# Battery_board_V4_4.net
KiCad netlist of a schematic drawn in EAGLE
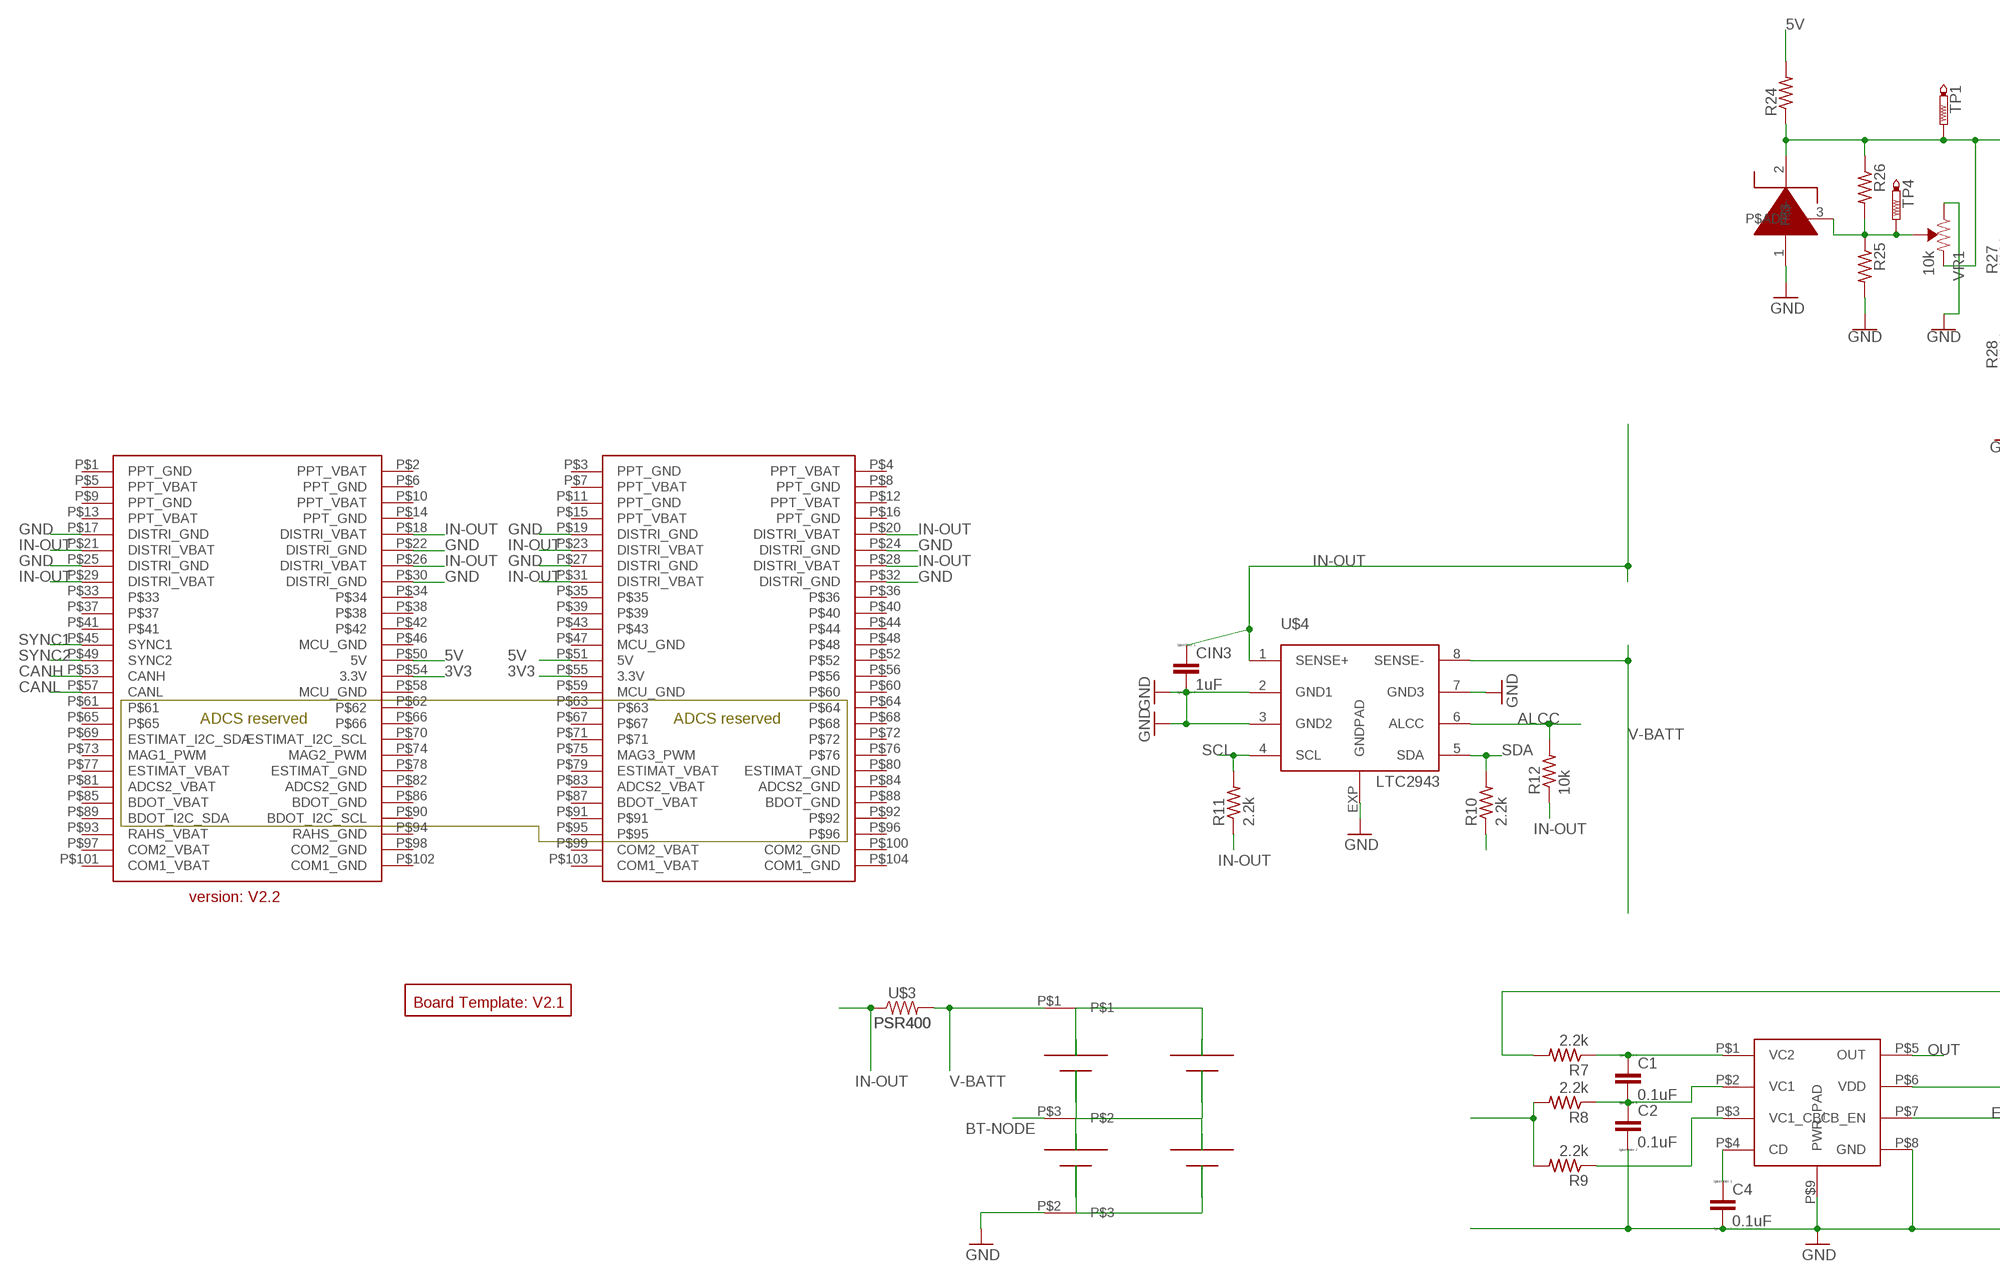
[diagram p0: schematic, sheet 1, part 1 of 2]
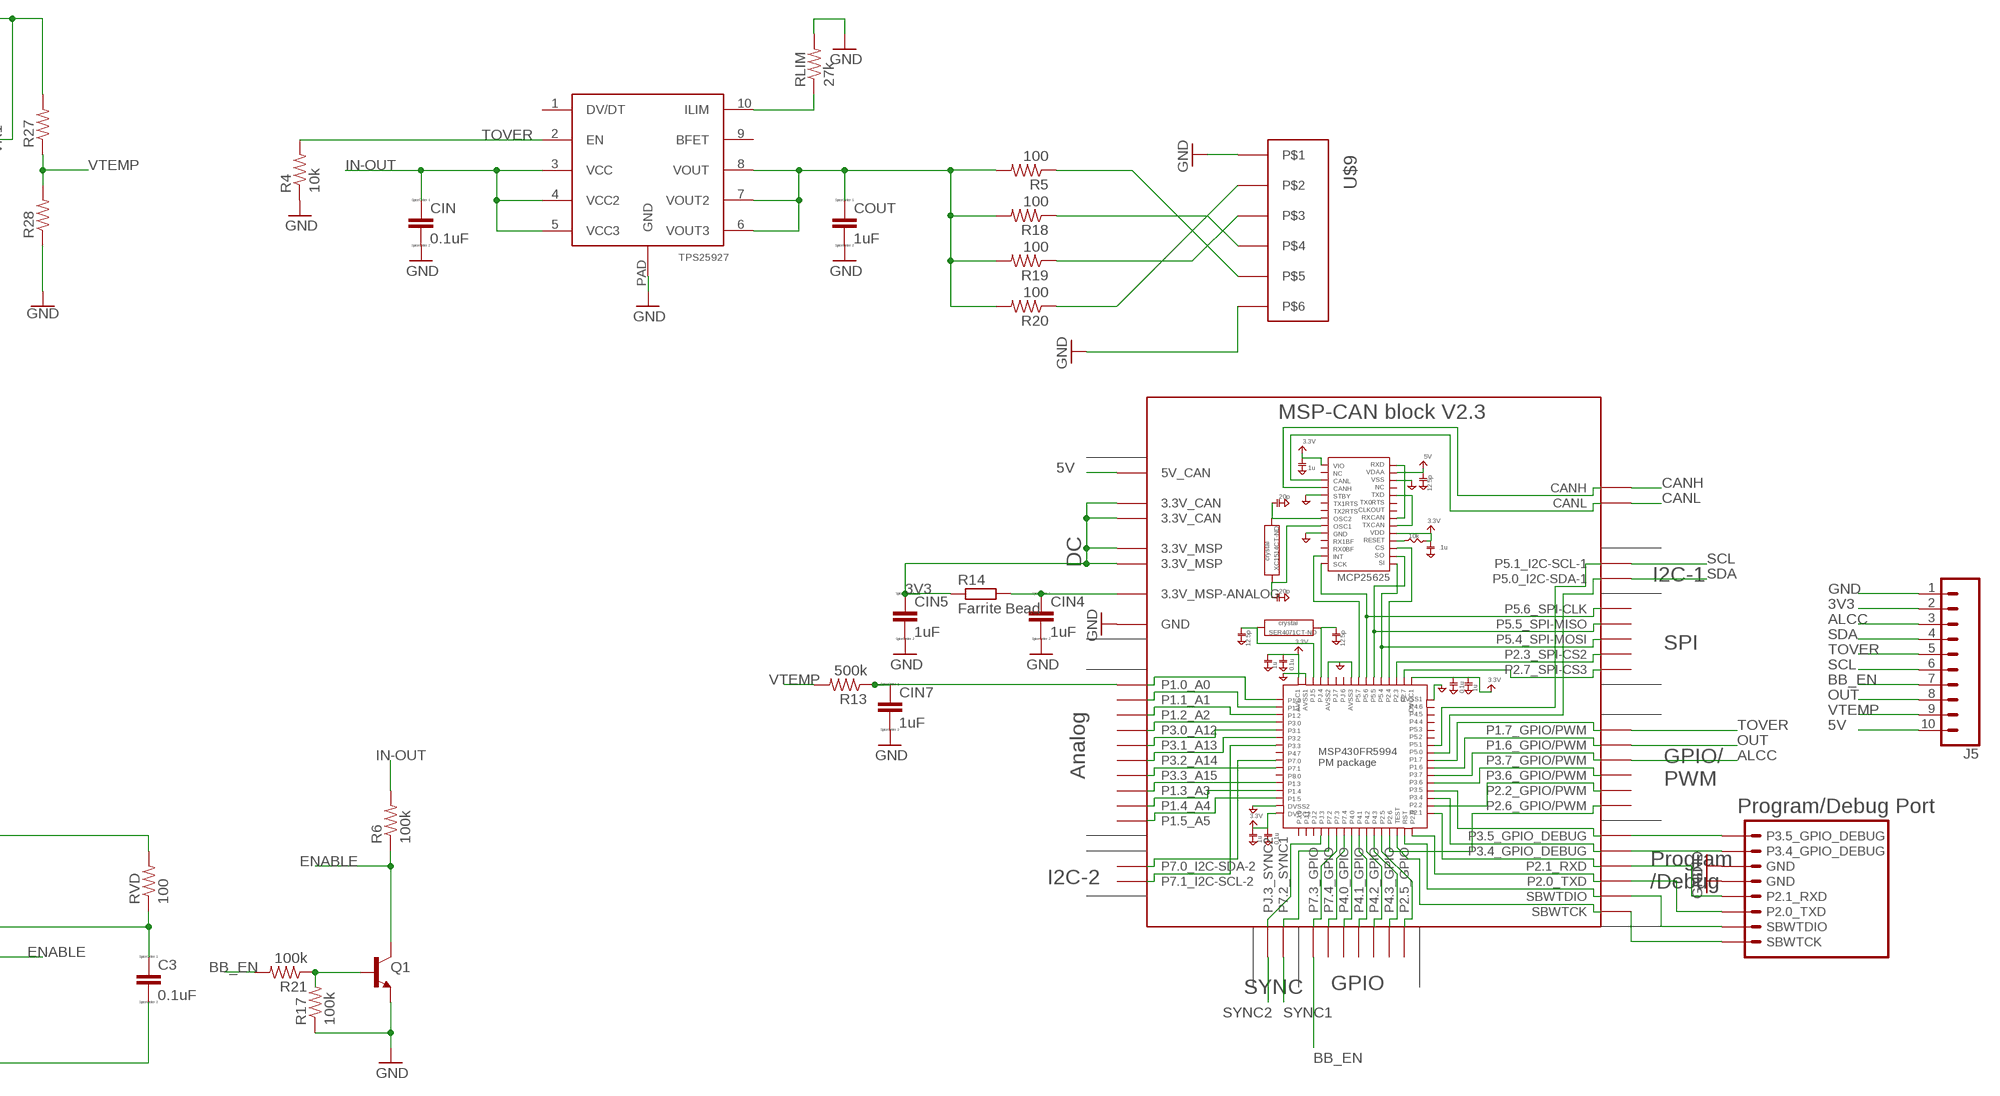
[diagram p1: schematic, sheet 1, part 2 of 2]

(export (version "E")
  (design (tool "Eeschema 10.0.6"))
  (components
    (comp (ref "C1")
      (value "0.1uF")
      (footprint "eagle-import:C0805")
      (libsource (lib "eagle-import") (part "C"))
    )
    (comp (ref "C2")
      (value "0.1uF")
      (footprint "eagle-import:C0805")
      (libsource (lib "eagle-import") (part "C"))
    )
    (comp (ref "C3")
      (value "0.1uF")
      (footprint "eagle-import:C0805")
      (libsource (lib "eagle-import") (part "C"))
    )
    (comp (ref "C4")
      (value "0.1uF")
      (footprint "eagle-import:C0805")
      (libsource (lib "eagle-import") (part "C"))
    )
    (comp (ref "CIN")
      (value "0.1uF")
      (footprint "eagle-import:C0805")
      (libsource (lib "eagle-import") (part "C"))
    )
    (comp (ref "CIN3")
      (value "1uF")
      (footprint "eagle-import:C0805")
      (libsource (lib "eagle-import") (part "C"))
    )
    (comp (ref "CIN4")
      (value "1uF")
      (footprint "eagle-import:C0805")
      (libsource (lib "eagle-import") (part "C"))
    )
    (comp (ref "CIN5")
      (value "1uF")
      (footprint "eagle-import:C0805")
      (libsource (lib "eagle-import") (part "C"))
    )
    (comp (ref "CIN7")
      (value "1uF")
      (footprint "eagle-import:C0805")
      (libsource (lib "eagle-import") (part "C"))
    )
    (comp (ref "COUT")
      (value "1uF")
      (footprint "eagle-import:C0805")
      (libsource (lib "eagle-import") (part "C"))
    )
    (comp (ref "J5")
      (value "CONN_10LOCK")
      (footprint "eagle-import:1X10_LOCK")
      (libsource (lib "eagle-import") (part "CONN_10LOCK"))
    )
    (comp (ref "Q1")
      (value "TRANS_NPN-MMBT2222AL")
      (footprint "eagle-import:SOT23-3")
      (libsource (lib "eagle-import") (part "TRANS_NPN-MMBT2222AL"))
    )
    (comp (ref "R4")
      (value "10k")
      (footprint "eagle-import:R0805")
      (libsource (lib "eagle-import") (part "R-US_R0805"))
    )
    (comp (ref "R5")
      (value "100")
      (footprint "eagle-import:R0805")
      (libsource (lib "eagle-import") (part "R-US_R0805"))
    )
    (comp (ref "R6")
      (value "100k")
      (footprint "eagle-import:R0805")
      (libsource (lib "eagle-import") (part "R-US_R0805"))
    )
    (comp (ref "R7")
      (value "2.2k")
      (footprint "eagle-import:R0805")
      (libsource (lib "eagle-import") (part "R-US_R0805"))
    )
    (comp (ref "R8")
      (value "2.2k")
      (footprint "eagle-import:R0805")
      (libsource (lib "eagle-import") (part "R-US_R0805"))
    )
    (comp (ref "R9")
      (value "2.2k")
      (footprint "eagle-import:R0805")
      (libsource (lib "eagle-import") (part "R-US_R0805"))
    )
    (comp (ref "R10")
      (value "2.2k")
      (footprint "eagle-import:R0805")
      (libsource (lib "eagle-import") (part "R-US_R0805"))
    )
    (comp (ref "R11")
      (value "2.2k")
      (footprint "eagle-import:R0805")
      (libsource (lib "eagle-import") (part "R-US_R0805"))
    )
    (comp (ref "R12")
      (value "10k")
      (footprint "eagle-import:R0805")
      (libsource (lib "eagle-import") (part "R-US_R0805"))
    )
    (comp (ref "R13")
      (value "500k")
      (footprint "eagle-import:R0805")
      (libsource (lib "eagle-import") (part "R-US_R0805"))
    )
    (comp (ref "R14")
      (value "Farrite Bead")
      (footprint "eagle-import:R1206")
      (libsource (lib "eagle-import") (part "R-EU_R1206"))
    )
    (comp (ref "R17")
      (value "100k")
      (footprint "eagle-import:M0805")
      (libsource (lib "eagle-import") (part "R-US_M0805"))
    )
    (comp (ref "R18")
      (value "100")
      (footprint "eagle-import:R0805")
      (libsource (lib "eagle-import") (part "R-US_R0805"))
    )
    (comp (ref "R19")
      (value "100")
      (footprint "eagle-import:R0805")
      (libsource (lib "eagle-import") (part "R-US_R0805"))
    )
    (comp (ref "R20")
      (value "100")
      (footprint "eagle-import:R0805")
      (libsource (lib "eagle-import") (part "R-US_R0805"))
    )
    (comp (ref "R21")
      (value "100k")
      (footprint "eagle-import:M0805")
      (libsource (lib "eagle-import") (part "R-US_M0805"))
    )
    (comp (ref "R24")
      (value "R-US_R0805")
      (footprint "eagle-import:R0805")
      (libsource (lib "eagle-import") (part "R-US_R0805"))
    )
    (comp (ref "R25")
      (value "R-US_R0805")
      (footprint "eagle-import:R0805")
      (libsource (lib "eagle-import") (part "R-US_R0805"))
    )
    (comp (ref "R26")
      (value "R-US_R0805")
      (footprint "eagle-import:R0805")
      (libsource (lib "eagle-import") (part "R-US_R0805"))
    )
    (comp (ref "R27")
      (value "R-US_R0805")
      (footprint "eagle-import:R0805")
      (libsource (lib "eagle-import") (part "R-US_R0805"))
    )
    (comp (ref "R28")
      (value "R-US_R0805")
      (footprint "eagle-import:R0805")
      (libsource (lib "eagle-import") (part "R-US_R0805"))
    )
    (comp (ref "RLIM")
      (value "27k")
      (footprint "eagle-import:R0805")
      (libsource (lib "eagle-import") (part "R-US_R0805"))
    )
    (comp (ref "RVD")
      (value "100")
      (footprint "eagle-import:R0805")
      (libsource (lib "eagle-import") (part "R-US_R0805"))
    )
    (comp (ref "TP1")
      (value "PTR1PAD1-13Y")
      (footprint "eagle-import:P1-13Y")
      (libsource (lib "eagle-import") (part "PTR1PAD1-13Y"))
    )
    (comp (ref "TP4")
      (value "PTR1PAD1-13Y")
      (footprint "eagle-import:P1-13Y")
      (libsource (lib "eagle-import") (part "PTR1PAD1-13Y"))
    )
    (comp (ref "U$1")
      (value "MSP-CAN_BLOCK")
      (footprint "eagle-import:MSP-CAN_BLOCK")
      (libsource (lib "eagle-import") (part "MSP-CAN_BLOCK"))
    )
    (comp (ref "U$2")
      (value "PROGRAM/DEBUG_PORT")
      (footprint "eagle-import:1X08_CONNECTOR")
      (libsource (lib "eagle-import") (part "PROGRAM/DEBUG_PORT"))
    )
    (comp (ref "U$3")
      (value "PSR400")
      (footprint "eagle-import:PSR400")
      (libsource (lib "eagle-import") (part "PSR400"))
    )
    (comp (ref "U$4")
      (value "LTC2943")
      (footprint "eagle-import:DFN8(3X3)LT")
      (libsource (lib "eagle-import") (part "LTC2943"))
    )
    (comp (ref "U$5")
      (value "TPS252927")
      (footprint "eagle-import:VSON10")
      (libsource (lib "eagle-import") (part "TPS252927"))
    )
    (comp (ref "U$6")
      (value "POWER_PACK")
      (footprint "eagle-import:BATTERY_PACK")
      (libsource (lib "eagle-import") (part "POWER_PACK"))
    )
    (comp (ref "U$7")
      (value "PC104_CONNECTOR")
      (footprint "eagle-import:PC104_CONNECTOR")
      (libsource (lib "eagle-import") (part "PC104_CONNECTOR"))
    )
    (comp (ref "U$8")
      (value "BQ29209")
      (footprint "eagle-import:VSON8")
      (libsource (lib "eagle-import") (part "BQ29209"))
    )
    (comp (ref "U$9")
      (value "PICOLOCK_6")
      (footprint "eagle-import:PICOLOCK_6")
      (libsource (lib "eagle-import") (part "PICOLOCK_6"))
    )
    (comp (ref "U$10")
      (value "LM135Z")
      (footprint "eagle-import:TO-92-3")
      (libsource (lib "eagle-import") (part "LM135Z"))
    )
    (comp (ref "U$11")
      (value "BOARD_TEMPLATE")
      (footprint "eagle-import:BOARD_TEMPLATE")
      (libsource (lib "eagle-import") (part "BOARD_TEMPLATE"))
    )
    (comp (ref "VR1")
      (value "10k")
      (footprint "eagle-import:TRIMPOT-SMD-TC33X")
      (libsource (lib "eagle-import") (part "TRIMPOT-SMD-3MM-OPEN-1/10W-25%"))
    )
  )
  (nets
    (net (code "1") (name "/3V3") (class "Default")
      (node (ref "CIN5") (pin "1") (pinfunction "1_1") (pintype "passive"))
      (node (ref "J5") (pin "2") (pinfunction "2_2") (pintype "passive"))
      (node (ref "R14") (pin "1") (pinfunction "1_1") (pintype "passive"))
      (node (ref "U$1") (pin "3.3V@CAN1") (pinfunction "3.3V_CAN_3.3V@CAN1") (pintype "bidirectional"))
      (node (ref "U$1") (pin "3.3V@CAN2") (pinfunction "3.3V_CAN_3.3V@CAN2") (pintype "bidirectional"))
      (node (ref "U$1") (pin "3.3V@MSP1") (pinfunction "3.3V_MSP_3.3V@MSP1") (pintype "bidirectional"))
      (node (ref "U$1") (pin "3.3V@MSP2") (pinfunction "3.3V_MSP_3.3V@MSP2") (pintype "bidirectional"))
      (node (ref "U$7") (pin "P$54") (pinfunction "3.3V_P$54") (pintype "bidirectional"))
      (node (ref "U$7") (pin "P$55") (pinfunction "3.3V_P$55") (pintype "bidirectional"))
    )
    (net (code "2") (name "/5V") (class "Default")
      (node (ref "J5") (pin "10") (pinfunction "10_10") (pintype "passive"))
      (node (ref "R24") (pin "2") (pinfunction "2_2") (pintype "passive"))
      (node (ref "U$1") (pin "5V") (pinfunction "5V_CAN_5V") (pintype "bidirectional"))
      (node (ref "U$7") (pin "P$50") (pinfunction "5V_P$50") (pintype "bidirectional"))
      (node (ref "U$7") (pin "P$51") (pinfunction "5V_P$51") (pintype "bidirectional"))
    )
    (net (code "3") (name "/ALCC") (class "Default")
      (node (ref "J5") (pin "3") (pinfunction "3_3") (pintype "passive"))
      (node (ref "R12") (pin "2") (pinfunction "2_2") (pintype "passive"))
      (node (ref "U$1") (pin "P3.7_GPIO/PWM") (pinfunction "P3.7_GPIO/PWM_P3.7_GPIO/PWM") (pintype "bidirectional"))
      (node (ref "U$4") (pin "6") (pinfunction "ALCC_6") (pintype "bidirectional"))
    )
    (net (code "4") (name "/BB_EN") (class "Default")
      (node (ref "J5") (pin "7") (pinfunction "7_7") (pintype "passive"))
      (node (ref "R21") (pin "2") (pinfunction "2_2") (pintype "passive"))
      (node (ref "U$1") (pin "P7.3_GPIO") (pinfunction "P7.3_GPIO_P7.3_GPIO") (pintype "bidirectional"))
    )
    (net (code "5") (name "/BT-NODE") (class "Default")
      (node (ref "R8") (pin "2") (pinfunction "2_2") (pintype "passive"))
      (node (ref "R9") (pin "2") (pinfunction "2_2") (pintype "passive"))
      (node (ref "U$6") (pin "P$3") (pinfunction "P$2_P$3") (pintype "bidirectional"))
    )
    (net (code "6") (name "/CANH") (class "Default")
      (node (ref "U$1") (pin "CANH") (pinfunction "CANH_CANH") (pintype "bidirectional"))
      (node (ref "U$7") (pin "P$53") (pinfunction "CANH_P$53") (pintype "bidirectional"))
    )
    (net (code "7") (name "/CANL") (class "Default")
      (node (ref "U$1") (pin "CANL") (pinfunction "CANL_CANL") (pintype "bidirectional"))
      (node (ref "U$7") (pin "P$57") (pinfunction "CANL_P$57") (pintype "bidirectional"))
    )
    (net (code "8") (name "/ENABLE") (class "Default")
      (node (ref "Q1") (pin "3") (pinfunction "C_3") (pintype "passive"))
      (node (ref "R6") (pin "1") (pinfunction "1_1") (pintype "passive"))
      (node (ref "U$8") (pin "P$7") (pinfunction "CB_EN_P$7") (pintype "bidirectional"))
    )
    (net (code "9") (name "/IN-OUT") (class "Default")
      (node (ref "CIN") (pin "1") (pinfunction "1_1") (pintype "passive"))
      (node (ref "CIN3") (pin "1") (pinfunction "1_1") (pintype "passive"))
      (node (ref "R10") (pin "1") (pinfunction "1_1") (pintype "passive"))
      (node (ref "R11") (pin "1") (pinfunction "1_1") (pintype "passive"))
      (node (ref "R12") (pin "1") (pinfunction "1_1") (pintype "passive"))
      (node (ref "R6") (pin "2") (pinfunction "2_2") (pintype "passive"))
      (node (ref "R7") (pin "2") (pinfunction "2_2") (pintype "passive"))
      (node (ref "RVD") (pin "2") (pinfunction "2_2") (pintype "passive"))
      (node (ref "U$3") (pin "P$1") (pinfunction "1_P$1") (pintype "passive"))
      (node (ref "U$4") (pin "1") (pinfunction "SENSE+_1") (pintype "bidirectional"))
      (node (ref "U$5") (pin "3") (pinfunction "VCC_3") (pintype "bidirectional"))
      (node (ref "U$5") (pin "4") (pinfunction "VCC2_4") (pintype "bidirectional"))
      (node (ref "U$5") (pin "5") (pinfunction "VCC3_5") (pintype "bidirectional"))
      (node (ref "U$7") (pin "P$18") (pinfunction "DISTRI_VBAT_P$18") (pintype "bidirectional"))
      (node (ref "U$7") (pin "P$20") (pinfunction "DISTRI_VBAT_P$20") (pintype "bidirectional"))
      (node (ref "U$7") (pin "P$21") (pinfunction "DISTRI_VBAT_P$21") (pintype "bidirectional"))
      (node (ref "U$7") (pin "P$23") (pinfunction "DISTRI_VBAT_P$23") (pintype "bidirectional"))
      (node (ref "U$7") (pin "P$26") (pinfunction "DISTRI_VBAT_P$26") (pintype "bidirectional"))
      (node (ref "U$7") (pin "P$28") (pinfunction "DISTRI_VBAT_P$28") (pintype "bidirectional"))
      (node (ref "U$7") (pin "P$29") (pinfunction "DISTRI_VBAT_P$29") (pintype "bidirectional"))
      (node (ref "U$7") (pin "P$31") (pinfunction "DISTRI_VBAT_P$31") (pintype "bidirectional"))
    )
    (net (code "10") (name "/OUT") (class "Default")
      (node (ref "J5") (pin "8") (pinfunction "8_8") (pintype "passive"))
      (node (ref "U$1") (pin "P1.6_GPIO/PWM") (pinfunction "P1.6_GPIO/PWM_P1.6_GPIO/PWM") (pintype "bidirectional"))
      (node (ref "U$8") (pin "P$5") (pinfunction "OUT_P$5") (pintype "bidirectional"))
    )
    (net (code "11") (name "/SCL") (class "Default")
      (node (ref "J5") (pin "6") (pinfunction "6_6") (pintype "passive"))
      (node (ref "R11") (pin "2") (pinfunction "2_2") (pintype "passive"))
      (node (ref "U$1") (pin "P5.1_I2C-SCL-1") (pinfunction "P5.1_I2C-SCL-1_P5.1_I2C-SCL-1") (pintype "bidirectional"))
      (node (ref "U$4") (pin "4") (pinfunction "SCL_4") (pintype "bidirectional"))
    )
    (net (code "12") (name "/SDA") (class "Default")
      (node (ref "J5") (pin "4") (pinfunction "4_4") (pintype "passive"))
      (node (ref "R10") (pin "2") (pinfunction "2_2") (pintype "passive"))
      (node (ref "U$1") (pin "P5.0_I2C-SDA-1") (pinfunction "P5.0_I2C-SDA-1_P5.0_I2C-SDA-1") (pintype "bidirectional"))
      (node (ref "U$4") (pin "5") (pinfunction "SDA_5") (pintype "bidirectional"))
    )
    (net (code "13") (name "/SYNC1") (class "Default")
      (node (ref "U$1") (pin "P7.2_SYNC1") (pinfunction "P7.2_SYNC1_P7.2_SYNC1") (pintype "bidirectional"))
      (node (ref "U$7") (pin "P$45") (pinfunction "SYNC1_P$45") (pintype "bidirectional"))
    )
    (net (code "14") (name "/SYNC2") (class "Default")
      (node (ref "U$1") (pin "PJ.3_SYNC2") (pinfunction "PJ.3_SYNC2_PJ.3_SYNC2") (pintype "bidirectional"))
      (node (ref "U$7") (pin "P$49") (pinfunction "SYNC2_P$49") (pintype "bidirectional"))
    )
    (net (code "15") (name "/TOVER") (class "Default")
      (node (ref "J5") (pin "5") (pinfunction "5_5") (pintype "passive"))
      (node (ref "R4") (pin "2") (pinfunction "2_2") (pintype "passive"))
      (node (ref "U$1") (pin "P1.7_GPIO/PWM") (pinfunction "P1.7_GPIO/PWM_P1.7_GPIO/PWM") (pintype "bidirectional"))
      (node (ref "U$5") (pin "2") (pinfunction "EN_2") (pintype "bidirectional"))
    )
    (net (code "16") (name "/V-BATT") (class "Default")
      (node (ref "U$3") (pin "P$2") (pinfunction "2_P$2") (pintype "passive"))
      (node (ref "U$4") (pin "8") (pinfunction "SENSE-_8") (pintype "bidirectional"))
      (node (ref "U$6") (pin "P$1") (pinfunction "P$1_P$1") (pintype "bidirectional"))
    )
    (net (code "17") (name "/VTEMP") (class "Default")
      (node (ref "J5") (pin "9") (pinfunction "9_9") (pintype "passive"))
      (node (ref "R13") (pin "2") (pinfunction "2_2") (pintype "passive"))
      (node (ref "R27") (pin "1") (pinfunction "1_1") (pintype "passive"))
      (node (ref "R28") (pin "2") (pinfunction "2_2") (pintype "passive"))
    )
    (net (code "18") (name "GND") (class "Default")
      (node (ref "C2") (pin "2") (pinfunction "2_2") (pintype "passive"))
      (node (ref "C3") (pin "2") (pinfunction "2_2") (pintype "passive"))
      (node (ref "C4") (pin "2") (pinfunction "2_2") (pintype "passive"))
      (node (ref "CIN") (pin "2") (pinfunction "2_2") (pintype "passive"))
      (node (ref "CIN3") (pin "2") (pinfunction "2_2") (pintype "passive"))
      (node (ref "CIN4") (pin "2") (pinfunction "2_2") (pintype "passive"))
      (node (ref "CIN5") (pin "2") (pinfunction "2_2") (pintype "passive"))
      (node (ref "CIN7") (pin "2") (pinfunction "2_2") (pintype "passive"))
      (node (ref "COUT") (pin "2") (pinfunction "2_2") (pintype "passive"))
      (node (ref "J5") (pin "1") (pinfunction "1_1") (pintype "passive"))
      (node (ref "Q1") (pin "2") (pinfunction "E_2") (pintype "passive"))
      (node (ref "R17") (pin "1") (pinfunction "1_1") (pintype "passive"))
      (node (ref "R25") (pin "2") (pinfunction "2_2") (pintype "passive"))
      (node (ref "R28") (pin "1") (pinfunction "1_1") (pintype "passive"))
      (node (ref "R4") (pin "1") (pinfunction "1_1") (pintype "passive"))
      (node (ref "RLIM") (pin "2") (pinfunction "2_2") (pintype "passive"))
      (node (ref "U$1") (pin "GND@1") (pinfunction "GND_GND@1") (pintype "bidirectional"))
      (node (ref "U$1") (pin "GND@10") (pinfunction "GND_GND@10") (pintype "bidirectional"))
      (node (ref "U$1") (pin "GND@11") (pinfunction "GND_GND@11") (pintype "bidirectional"))
      (node (ref "U$1") (pin "GND@12") (pinfunction "GND_GND@12") (pintype "bidirectional"))
      (node (ref "U$1") (pin "GND@13") (pinfunction "GND_GND@13") (pintype "bidirectional"))
      (node (ref "U$1") (pin "GND@14") (pinfunction "GND_GND@14") (pintype "bidirectional"))
      (node (ref "U$1") (pin "GND@15") (pinfunction "GND_GND@15") (pintype "bidirectional"))
      (node (ref "U$1") (pin "GND@16") (pinfunction "GND_GND@16") (pintype "bidirectional"))
      (node (ref "U$1") (pin "GND@17") (pinfunction "GND_GND@17") (pintype "bidirectional"))
      (node (ref "U$1") (pin "GND@2") (pinfunction "GND_GND@2") (pintype "bidirectional"))
      (node (ref "U$1") (pin "GND@26") (pinfunction "GND_GND@26") (pintype "bidirectional"))
      (node (ref "U$1") (pin "GND@3") (pinfunction "GND_GND@3") (pintype "bidirectional"))
      (node (ref "U$1") (pin "GND@4") (pinfunction "GND_GND@4") (pintype "bidirectional"))
      (node (ref "U$1") (pin "GND@5") (pinfunction "GND_GND@5") (pintype "bidirectional"))
      (node (ref "U$1") (pin "GND@7") (pinfunction "GND_GND@7") (pintype "bidirectional"))
      (node (ref "U$1") (pin "GND@8") (pinfunction "GND_GND@8") (pintype "bidirectional"))
      (node (ref "U$1") (pin "GND@9") (pinfunction "GND_GND@9") (pintype "bidirectional"))
      (node (ref "U$10") (pin "1") (pinfunction "P$-_1") (pintype "bidirectional"))
      (node (ref "U$2") (pin "5") (pinfunction "GND_5") (pintype "bidirectional"))
      (node (ref "U$2") (pin "6") (pinfunction "GND_6") (pintype "bidirectional"))
      (node (ref "U$4") (pin "2") (pinfunction "GND1_2") (pintype "bidirectional"))
      (node (ref "U$4") (pin "3") (pinfunction "GND2_3") (pintype "bidirectional"))
      (node (ref "U$4") (pin "7") (pinfunction "GND3_7") (pintype "bidirectional"))
      (node (ref "U$4") (pin "EXP") (pinfunction "GNDPAD_EXP") (pintype "bidirectional"))
      (node (ref "U$5") (pin "PAD") (pinfunction "GND_PAD") (pintype "bidirectional"))
      (node (ref "U$6") (pin "P$2") (pinfunction "P$3_P$2") (pintype "bidirectional"))
      (node (ref "U$7") (pin "P$17") (pinfunction "DISTRI_GND_P$17") (pintype "bidirectional"))
      (node (ref "U$7") (pin "P$19") (pinfunction "DISTRI_GND_P$19") (pintype "bidirectional"))
      (node (ref "U$7") (pin "P$22") (pinfunction "DISTRI_GND_P$22") (pintype "bidirectional"))
      (node (ref "U$7") (pin "P$24") (pinfunction "DISTRI_GND_P$24") (pintype "bidirectional"))
      (node (ref "U$7") (pin "P$25") (pinfunction "DISTRI_GND_P$25") (pintype "bidirectional"))
      (node (ref "U$7") (pin "P$27") (pinfunction "DISTRI_GND_P$27") (pintype "bidirectional"))
      (node (ref "U$7") (pin "P$30") (pinfunction "DISTRI_GND_P$30") (pintype "bidirectional"))
      (node (ref "U$7") (pin "P$32") (pinfunction "DISTRI_GND_P$32") (pintype "bidirectional"))
      (node (ref "U$8") (pin "P$8") (pinfunction "GND_P$8") (pintype "bidirectional"))
      (node (ref "U$8") (pin "P$9") (pinfunction "PWR_PAD_P$9") (pintype "bidirectional"))
      (node (ref "U$9") (pin "P$1") (pinfunction "P$1_P$1") (pintype "bidirectional"))
      (node (ref "U$9") (pin "P$6") (pinfunction "P$6_P$6") (pintype "bidirectional"))
      (node (ref "VR1") (pin "1") (pinfunction "CW_1") (pintype "passive"))
    )
    (net (code "19") (name "Net-(CIN7-Pad1)") (class "Default")
      (node (ref "CIN7") (pin "1") (pinfunction "1_1") (pintype "passive"))
      (node (ref "R13") (pin "1") (pinfunction "1_1") (pintype "passive"))
      (node (ref "U$1") (pin "P1.0_A0") (pinfunction "P1.0_A0_P1.0_A0") (pintype "bidirectional"))
    )
    (net (code "20") (name "Net-(Q1-B)") (class "Default")
      (node (ref "Q1") (pin "1") (pinfunction "B_1") (pintype "passive"))
      (node (ref "R17") (pin "2") (pinfunction "2_2") (pintype "passive"))
      (node (ref "R21") (pin "1") (pinfunction "1_1") (pintype "passive"))
    )
    (net (code "21") (name "Net-(R5-Pad1)") (class "Default")
      (node (ref "R5") (pin "1") (pinfunction "1_1") (pintype "passive"))
      (node (ref "U$9") (pin "P$5") (pinfunction "P$5_P$5") (pintype "bidirectional"))
    )
    (net (code "22") (name "Net-(R18-Pad1)") (class "Default")
      (node (ref "R18") (pin "1") (pinfunction "1_1") (pintype "passive"))
      (node (ref "U$9") (pin "P$4") (pinfunction "P$4_P$4") (pintype "bidirectional"))
    )
    (net (code "23") (name "Net-(R19-Pad1)") (class "Default")
      (node (ref "R19") (pin "1") (pinfunction "1_1") (pintype "passive"))
      (node (ref "U$9") (pin "P$3") (pinfunction "P$3_P$3") (pintype "bidirectional"))
    )
    (net (code "24") (name "Net-(R20-Pad1)") (class "Default")
      (node (ref "R20") (pin "1") (pinfunction "1_1") (pintype "passive"))
      (node (ref "U$9") (pin "P$2") (pinfunction "P$2_P$2") (pintype "bidirectional"))
    )
    (net (code "25") (name "Net-(U$1-3.3V_MSP-ANALOG)") (class "Default")
      (node (ref "CIN4") (pin "1") (pinfunction "1_1") (pintype "passive"))
      (node (ref "R14") (pin "2") (pinfunction "2_2") (pintype "passive"))
      (node (ref "U$1") (pin "3.3V_ANALOG@MSP2") (pinfunction "3.3V_MSP-ANALOG_3.3V_ANALOG@MSP2") (pintype "bidirectional"))
    )
    (net (code "26") (name "Net-(U$1-PadSBWTCK)") (class "Default")
      (node (ref "U$1") (pin "SBWTCK") (pinfunction "SBWTCK_SBWTCK") (pintype "bidirectional"))
      (node (ref "U$2") (pin "SBWTCK") (pinfunction "SBWTCK_SBWTCK") (pintype "bidirectional"))
    )
    (net (code "27") (name "Net-(U$2-P2.0_TXD)") (class "Default")
      (node (ref "U$1") (pin "P2.0_TXD") (pinfunction "P2.0_TXD_P2.0_TXD") (pintype "bidirectional"))
      (node (ref "U$2") (pin "3") (pinfunction "P2.0_TXD_3") (pintype "bidirectional"))
    )
    (net (code "28") (name "Net-(U$2-P2.1_RXD)") (class "Default")
      (node (ref "U$1") (pin "P2.1_RXD") (pinfunction "P2.1_RXD_P2.1_RXD") (pintype "bidirectional"))
      (node (ref "U$2") (pin "4") (pinfunction "P2.1_RXD_4") (pintype "bidirectional"))
    )
    (net (code "29") (name "Net-(U$2-P3.4_GPIO_DEBUG)") (class "Default")
      (node (ref "U$1") (pin "P3.4_GPIO_DEBUG") (pinfunction "P3.4_GPIO_DEBUG_P3.4_GPIO_DEBUG") (pintype "bidirectional"))
      (node (ref "U$2") (pin "7") (pinfunction "P3.4_GPIO_DEBUG_7") (pintype "bidirectional"))
    )
    (net (code "30") (name "Net-(U$2-P3.5_GPIO_DEBUG)") (class "Default")
      (node (ref "U$1") (pin "P3.5_GPIO_DEBUG") (pinfunction "P3.5_GPIO_DEBUG_P3.5_GPIO_DEBUG") (pintype "bidirectional"))
      (node (ref "U$2") (pin "8") (pinfunction "P3.5_GPIO_DEBUG_8") (pintype "bidirectional"))
    )
    (net (code "31") (name "Net-(U$2-SBWTDIO)") (class "Default")
      (node (ref "U$1") (pin "SBWTDIO") (pinfunction "SBWTDIO_SBWTDIO") (pintype "bidirectional"))
      (node (ref "U$2") (pin "2") (pinfunction "SBWTDIO_2") (pintype "bidirectional"))
    )
    (net (code "32") (name "Net-(U$5-ILIM)") (class "Default")
      (node (ref "RLIM") (pin "1") (pinfunction "1_1") (pintype "passive"))
      (node (ref "U$5") (pin "10") (pinfunction "ILIM_10") (pintype "bidirectional"))
    )
    (net (code "33") (name "Net-(U$5-VOUT)") (class "Default")
      (node (ref "COUT") (pin "1") (pinfunction "1_1") (pintype "passive"))
      (node (ref "R18") (pin "2") (pinfunction "2_2") (pintype "passive"))
      (node (ref "R19") (pin "2") (pinfunction "2_2") (pintype "passive"))
      (node (ref "R20") (pin "2") (pinfunction "2_2") (pintype "passive"))
      (node (ref "R5") (pin "2") (pinfunction "2_2") (pintype "passive"))
      (node (ref "U$5") (pin "6") (pinfunction "VOUT3_6") (pintype "bidirectional"))
      (node (ref "U$5") (pin "7") (pinfunction "VOUT2_7") (pintype "bidirectional"))
      (node (ref "U$5") (pin "8") (pinfunction "VOUT_8") (pintype "bidirectional"))
    )
    (net (code "34") (name "Net-(U$8-CD)") (class "Default")
      (node (ref "C4") (pin "1") (pinfunction "1_1") (pintype "passive"))
      (node (ref "U$8") (pin "P$4") (pinfunction "CD_P$4") (pintype "bidirectional"))
    )
    (net (code "35") (name "Net-(U$8-VC1)") (class "Default")
      (node (ref "C1") (pin "2") (pinfunction "2_2") (pintype "passive"))
      (node (ref "C2") (pin "1") (pinfunction "1_1") (pintype "passive"))
      (node (ref "R8") (pin "1") (pinfunction "1_1") (pintype "passive"))
      (node (ref "U$8") (pin "P$2") (pinfunction "VC1_P$2") (pintype "bidirectional"))
    )
    (net (code "36") (name "Net-(U$8-VC1_CB)") (class "Default")
      (node (ref "R9") (pin "1") (pinfunction "1_1") (pintype "passive"))
      (node (ref "U$8") (pin "P$3") (pinfunction "VC1_CB_P$3") (pintype "bidirectional"))
    )
    (net (code "37") (name "Net-(U$8-VC2)") (class "Default")
      (node (ref "C1") (pin "1") (pinfunction "1_1") (pintype "passive"))
      (node (ref "R7") (pin "1") (pinfunction "1_1") (pintype "passive"))
      (node (ref "U$8") (pin "P$1") (pinfunction "VC2_P$1") (pintype "bidirectional"))
    )
    (net (code "38") (name "Net-(U$8-VDD)") (class "Default")
      (node (ref "C3") (pin "1") (pinfunction "1_1") (pintype "passive"))
      (node (ref "RVD") (pin "1") (pinfunction "1_1") (pintype "passive"))
      (node (ref "U$8") (pin "P$6") (pinfunction "VDD_P$6") (pintype "bidirectional"))
    )
    (net (code "39") (name "Net-(U$10-P$+)") (class "Default")
      (node (ref "R24") (pin "1") (pinfunction "1_1") (pintype "passive"))
      (node (ref "R26") (pin "1") (pinfunction "1_1") (pintype "passive"))
      (node (ref "R27") (pin "2") (pinfunction "2_2") (pintype "passive"))
      (node (ref "TP1") (pin "TP") (pinfunction "TP_TP") (pintype "input"))
      (node (ref "U$10") (pin "2") (pinfunction "P$+_2") (pintype "bidirectional"))
      (node (ref "VR1") (pin "3") (pinfunction "CCW_3") (pintype "passive"))
    )
    (net (code "40") (name "Net-(U$10-P$ADJ)") (class "Default")
      (node (ref "R25") (pin "1") (pinfunction "1_1") (pintype "passive"))
      (node (ref "R26") (pin "2") (pinfunction "2_2") (pintype "passive"))
      (node (ref "TP4") (pin "TP") (pinfunction "TP_TP") (pintype "input"))
      (node (ref "U$10") (pin "3") (pinfunction "P$ADJ_3") (pintype "bidirectional"))
      (node (ref "VR1") (pin "2") (pinfunction "WIPER_2") (pintype "passive"))
    )
    (net (code "41") (name "unconnected-(U$1-P2.3_SPI-CS2-PadP2.4_SPI-CS2)") (class "Default")
      (node (ref "U$1") (pin "P2.4_SPI-CS2") (pinfunction "P2.3_SPI-CS2_P2.4_SPI-CS2") (pintype "bidirectional"))
    )
    (net (code "42") (name "unconnected-(U$1-PadP1.1_A1)") (class "Default")
      (node (ref "U$1") (pin "P1.1_A1") (pinfunction "P1.1_A1_P1.1_A1") (pintype "bidirectional"))
    )
    (net (code "43") (name "unconnected-(U$1-PadP1.2_A2)") (class "Default")
      (node (ref "U$1") (pin "P1.2_A2") (pinfunction "P1.2_A2_P1.2_A2") (pintype "bidirectional"))
    )
    (net (code "44") (name "unconnected-(U$1-PadP1.3_A3)") (class "Default")
      (node (ref "U$1") (pin "P1.3_A3") (pinfunction "P1.3_A3_P1.3_A3") (pintype "bidirectional"))
    )
    (net (code "45") (name "unconnected-(U$1-PadP1.4_A4)") (class "Default")
      (node (ref "U$1") (pin "P1.4_A4") (pinfunction "P1.4_A4_P1.4_A4") (pintype "bidirectional"))
    )
    (net (code "46") (name "unconnected-(U$1-PadP1.5_A5)") (class "Default")
      (node (ref "U$1") (pin "P1.5_A5") (pinfunction "P1.5_A5_P1.5_A5") (pintype "bidirectional"))
    )
    (net (code "47") (name "unconnected-(U$1-PadP2.2_GPIO{slash}PWM)") (class "Default")
      (node (ref "U$1") (pin "P2.2_GPIO/PWM") (pinfunction "P2.2_GPIO/PWM_P2.2_GPIO/PWM") (pintype "bidirectional"))
    )
    (net (code "48") (name "unconnected-(U$1-PadP2.5_GPIO)") (class "Default")
      (node (ref "U$1") (pin "P2.5_GPIO") (pinfunction "P2.5_GPIO_P2.5_GPIO") (pintype "bidirectional"))
    )
    (net (code "49") (name "unconnected-(U$1-PadP2.6_GPIO{slash}PWM)") (class "Default")
      (node (ref "U$1") (pin "P2.6_GPIO/PWM") (pinfunction "P2.6_GPIO/PWM_P2.6_GPIO/PWM") (pintype "bidirectional"))
    )
    (net (code "50") (name "unconnected-(U$1-PadP2.7_SPI-CS3)") (class "Default")
      (node (ref "U$1") (pin "P2.7_SPI-CS3") (pinfunction "P2.7_SPI-CS3_P2.7_SPI-CS3") (pintype "bidirectional"))
    )
    (net (code "51") (name "unconnected-(U$1-PadP3.0_A12)") (class "Default")
      (node (ref "U$1") (pin "P3.0_A12") (pinfunction "P3.0_A12_P3.0_A12") (pintype "bidirectional"))
    )
    (net (code "52") (name "unconnected-(U$1-PadP3.1_A13)") (class "Default")
      (node (ref "U$1") (pin "P3.1_A13") (pinfunction "P3.1_A13_P3.1_A13") (pintype "bidirectional"))
    )
    (net (code "53") (name "unconnected-(U$1-PadP3.2_A14)") (class "Default")
      (node (ref "U$1") (pin "P3.2_A14") (pinfunction "P3.2_A14_P3.2_A14") (pintype "bidirectional"))
    )
    (net (code "54") (name "unconnected-(U$1-PadP3.3_A15)") (class "Default")
      (node (ref "U$1") (pin "P3.3_A15") (pinfunction "P3.3_A15_P3.3_A15") (pintype "bidirectional"))
    )
    (net (code "55") (name "unconnected-(U$1-PadP3.6_GPIO{slash}PWM)") (class "Default")
      (node (ref "U$1") (pin "P3.6_GPIO/PWM") (pinfunction "P3.6_GPIO/PWM_P3.6_GPIO/PWM") (pintype "bidirectional"))
    )
    (net (code "56") (name "unconnected-(U$1-PadP4.0_GPIO)") (class "Default")
      (node (ref "U$1") (pin "P4.0_GPIO") (pinfunction "P4.0_GPIO_P4.0_GPIO") (pintype "bidirectional"))
    )
    (net (code "57") (name "unconnected-(U$1-PadP4.1_GPIO)") (class "Default")
      (node (ref "U$1") (pin "P4.1_GPIO") (pinfunction "P4.1_GPIO_P4.1_GPIO") (pintype "bidirectional"))
    )
    (net (code "58") (name "unconnected-(U$1-PadP4.2_GPIO)") (class "Default")
      (node (ref "U$1") (pin "P4.2_GPIO") (pinfunction "P4.2_GPIO_P4.2_GPIO") (pintype "bidirectional"))
    )
    (net (code "59") (name "unconnected-(U$1-PadP4.3_GPIO)") (class "Default")
      (node (ref "U$1") (pin "P4.3_GPIO") (pinfunction "P4.3_GPIO_P4.3_GPIO") (pintype "bidirectional"))
    )
    (net (code "60") (name "unconnected-(U$1-PadP5.4_SPI-MOSI)") (class "Default")
      (node (ref "U$1") (pin "P5.4_SPI-MOSI") (pinfunction "P5.4_SPI-MOSI_P5.4_SPI-MOSI") (pintype "bidirectional"))
    )
    (net (code "61") (name "unconnected-(U$1-PadP5.5_SPI-MISO)") (class "Default")
      (node (ref "U$1") (pin "P5.5_SPI-MISO") (pinfunction "P5.5_SPI-MISO_P5.5_SPI-MISO") (pintype "bidirectional"))
    )
    (net (code "62") (name "unconnected-(U$1-PadP5.6_SPI-CLK)") (class "Default")
      (node (ref "U$1") (pin "P5.6_SPI-CLK") (pinfunction "P5.6_SPI-CLK_P5.6_SPI-CLK") (pintype "bidirectional"))
    )
    (net (code "63") (name "unconnected-(U$1-PadP7.0_I2C-SDA-2)") (class "Default")
      (node (ref "U$1") (pin "P7.0_I2C-SDA-2") (pinfunction "P7.0_I2C-SDA-2_P7.0_I2C-SDA-2") (pintype "bidirectional"))
    )
    (net (code "64") (name "unconnected-(U$1-PadP7.1_I2C-SCL-2)") (class "Default")
      (node (ref "U$1") (pin "P7.1_I2C-SCL-2") (pinfunction "P7.1_I2C-SCL-2_P7.1_I2C-SCL-2") (pintype "bidirectional"))
    )
    (net (code "65") (name "unconnected-(U$1-PadP7.4_GPIO)") (class "Default")
      (node (ref "U$1") (pin "P7.4_GPIO") (pinfunction "P7.4_GPIO_P7.4_GPIO") (pintype "bidirectional"))
    )
    (net (code "66") (name "unconnected-(U$5-BFET-Pad9)") (class "Default")
      (node (ref "U$5") (pin "9") (pinfunction "BFET_9") (pintype "bidirectional"))
    )
    (net (code "67") (name "unconnected-(U$5-DV{slash}DT-Pad1)") (class "Default")
      (node (ref "U$5") (pin "1") (pinfunction "DV/DT_1") (pintype "bidirectional"))
    )
    (net (code "68") (name "unconnected-(U$7-ADCS2_GND-PadP$82)") (class "Default")
      (node (ref "U$7") (pin "P$82") (pinfunction "ADCS2_GND_P$82") (pintype "bidirectional"))
    )
    (net (code "69") (name "unconnected-(U$7-ADCS2_GND-PadP$84)") (class "Default")
      (node (ref "U$7") (pin "P$84") (pinfunction "ADCS2_GND_P$84") (pintype "bidirectional"))
    )
    (net (code "70") (name "unconnected-(U$7-ADCS2_VBAT-PadP$81)") (class "Default")
      (node (ref "U$7") (pin "P$81") (pinfunction "ADCS2_VBAT_P$81") (pintype "bidirectional"))
    )
    (net (code "71") (name "unconnected-(U$7-ADCS2_VBAT-PadP$83)") (class "Default")
      (node (ref "U$7") (pin "P$83") (pinfunction "ADCS2_VBAT_P$83") (pintype "bidirectional"))
    )
    (net (code "72") (name "unconnected-(U$7-BDOT_GND-PadP$86)") (class "Default")
      (node (ref "U$7") (pin "P$86") (pinfunction "BDOT_GND_P$86") (pintype "bidirectional"))
    )
    (net (code "73") (name "unconnected-(U$7-BDOT_GND-PadP$88)") (class "Default")
      (node (ref "U$7") (pin "P$88") (pinfunction "BDOT_GND_P$88") (pintype "bidirectional"))
    )
    (net (code "74") (name "unconnected-(U$7-BDOT_I2C_SCL-PadP$90)") (class "Default")
      (node (ref "U$7") (pin "P$90") (pinfunction "BDOT_I2C_SCL_P$90") (pintype "bidirectional"))
    )
    (net (code "75") (name "unconnected-(U$7-BDOT_I2C_SDA-PadP$89)") (class "Default")
      (node (ref "U$7") (pin "P$89") (pinfunction "BDOT_I2C_SDA_P$89") (pintype "bidirectional"))
    )
    (net (code "76") (name "unconnected-(U$7-BDOT_VBAT-PadP$85)") (class "Default")
      (node (ref "U$7") (pin "P$85") (pinfunction "BDOT_VBAT_P$85") (pintype "bidirectional"))
    )
    (net (code "77") (name "unconnected-(U$7-BDOT_VBAT-PadP$87)") (class "Default")
      (node (ref "U$7") (pin "P$87") (pinfunction "BDOT_VBAT_P$87") (pintype "bidirectional"))
    )
    (net (code "78") (name "unconnected-(U$7-COM1_GND-PadP$102)") (class "Default")
      (node (ref "U$7") (pin "P$102") (pinfunction "COM1_GND_P$102") (pintype "bidirectional"))
    )
    (net (code "79") (name "unconnected-(U$7-COM1_GND-PadP$104)") (class "Default")
      (node (ref "U$7") (pin "P$104") (pinfunction "COM1_GND_P$104") (pintype "bidirectional"))
    )
    (net (code "80") (name "unconnected-(U$7-COM1_VBAT-PadP$101)") (class "Default")
      (node (ref "U$7") (pin "P$101") (pinfunction "COM1_VBAT_P$101") (pintype "bidirectional"))
    )
    (net (code "81") (name "unconnected-(U$7-COM1_VBAT-PadP$103)") (class "Default")
      (node (ref "U$7") (pin "P$103") (pinfunction "COM1_VBAT_P$103") (pintype "bidirectional"))
    )
    (net (code "82") (name "unconnected-(U$7-COM2_GND-PadP$98)") (class "Default")
      (node (ref "U$7") (pin "P$98") (pinfunction "COM2_GND_P$98") (pintype "bidirectional"))
    )
    (net (code "83") (name "unconnected-(U$7-COM2_GND-PadP$100)") (class "Default")
      (node (ref "U$7") (pin "P$100") (pinfunction "COM2_GND_P$100") (pintype "bidirectional"))
    )
    (net (code "84") (name "unconnected-(U$7-COM2_VBAT-PadP$97)") (class "Default")
      (node (ref "U$7") (pin "P$97") (pinfunction "COM2_VBAT_P$97") (pintype "bidirectional"))
    )
    (net (code "85") (name "unconnected-(U$7-COM2_VBAT-PadP$99)") (class "Default")
      (node (ref "U$7") (pin "P$99") (pinfunction "COM2_VBAT_P$99") (pintype "bidirectional"))
    )
    (net (code "86") (name "unconnected-(U$7-ESTIMAT_GND-PadP$78)") (class "Default")
      (node (ref "U$7") (pin "P$78") (pinfunction "ESTIMAT_GND_P$78") (pintype "bidirectional"))
    )
    (net (code "87") (name "unconnected-(U$7-ESTIMAT_GND-PadP$80)") (class "Default")
      (node (ref "U$7") (pin "P$80") (pinfunction "ESTIMAT_GND_P$80") (pintype "bidirectional"))
    )
    (net (code "88") (name "unconnected-(U$7-ESTIMAT_I2C_SCL-PadP$70)") (class "Default")
      (node (ref "U$7") (pin "P$70") (pinfunction "ESTIMAT_I2C_SCL_P$70") (pintype "bidirectional"))
    )
    (net (code "89") (name "unconnected-(U$7-ESTIMAT_I2C_SDA-PadP$69)") (class "Default")
      (node (ref "U$7") (pin "P$69") (pinfunction "ESTIMAT_I2C_SDA_P$69") (pintype "bidirectional"))
    )
    (net (code "90") (name "unconnected-(U$7-ESTIMAT_VBAT-PadP$77)") (class "Default")
      (node (ref "U$7") (pin "P$77") (pinfunction "ESTIMAT_VBAT_P$77") (pintype "bidirectional"))
    )
    (net (code "91") (name "unconnected-(U$7-ESTIMAT_VBAT-PadP$79)") (class "Default")
      (node (ref "U$7") (pin "P$79") (pinfunction "ESTIMAT_VBAT_P$79") (pintype "bidirectional"))
    )
    (net (code "92") (name "unconnected-(U$7-MAG1_PWM-PadP$73)") (class "Default")
      (node (ref "U$7") (pin "P$73") (pinfunction "MAG1_PWM_P$73") (pintype "bidirectional"))
    )
    (net (code "93") (name "unconnected-(U$7-MAG2_PWM-PadP$74)") (class "Default")
      (node (ref "U$7") (pin "P$74") (pinfunction "MAG2_PWM_P$74") (pintype "bidirectional"))
    )
    (net (code "94") (name "unconnected-(U$7-MAG3_PWM-PadP$75)") (class "Default")
      (node (ref "U$7") (pin "P$75") (pinfunction "MAG3_PWM_P$75") (pintype "bidirectional"))
    )
    (net (code "95") (name "unconnected-(U$7-MCU_GND-PadP$46)") (class "Default")
      (node (ref "U$7") (pin "P$46") (pinfunction "MCU_GND_P$46") (pintype "bidirectional"))
    )
    (net (code "96") (name "unconnected-(U$7-MCU_GND-PadP$47)") (class "Default")
      (node (ref "U$7") (pin "P$47") (pinfunction "MCU_GND_P$47") (pintype "bidirectional"))
    )
    (net (code "97") (name "unconnected-(U$7-MCU_GND-PadP$58)") (class "Default")
      (node (ref "U$7") (pin "P$58") (pinfunction "MCU_GND_P$58") (pintype "bidirectional"))
    )
    (net (code "98") (name "unconnected-(U$7-MCU_GND-PadP$59)") (class "Default")
      (node (ref "U$7") (pin "P$59") (pinfunction "MCU_GND_P$59") (pintype "bidirectional"))
    )
    (net (code "99") (name "unconnected-(U$7-PPT_GND-PadP$1)") (class "Default")
      (node (ref "U$7") (pin "P$1") (pinfunction "PPT_GND_P$1") (pintype "bidirectional"))
    )
    (net (code "100") (name "unconnected-(U$7-PPT_GND-PadP$3)") (class "Default")
      (node (ref "U$7") (pin "P$3") (pinfunction "PPT_GND_P$3") (pintype "bidirectional"))
    )
    (net (code "101") (name "unconnected-(U$7-PPT_GND-PadP$6)") (class "Default")
      (node (ref "U$7") (pin "P$6") (pinfunction "PPT_GND_P$6") (pintype "bidirectional"))
    )
    (net (code "102") (name "unconnected-(U$7-PPT_GND-PadP$8)") (class "Default")
      (node (ref "U$7") (pin "P$8") (pinfunction "PPT_GND_P$8") (pintype "bidirectional"))
    )
    (net (code "103") (name "unconnected-(U$7-PPT_GND-PadP$9)") (class "Default")
      (node (ref "U$7") (pin "P$9") (pinfunction "PPT_GND_P$9") (pintype "bidirectional"))
    )
    (net (code "104") (name "unconnected-(U$7-PPT_GND-PadP$11)") (class "Default")
      (node (ref "U$7") (pin "P$11") (pinfunction "PPT_GND_P$11") (pintype "bidirectional"))
    )
    (net (code "105") (name "unconnected-(U$7-PPT_GND-PadP$14)") (class "Default")
      (node (ref "U$7") (pin "P$14") (pinfunction "PPT_GND_P$14") (pintype "bidirectional"))
    )
    (net (code "106") (name "unconnected-(U$7-PPT_GND-PadP$16)") (class "Default")
      (node (ref "U$7") (pin "P$16") (pinfunction "PPT_GND_P$16") (pintype "bidirectional"))
    )
    (net (code "107") (name "unconnected-(U$7-PPT_VBAT-PadP$2)") (class "Default")
      (node (ref "U$7") (pin "P$2") (pinfunction "PPT_VBAT_P$2") (pintype "bidirectional"))
    )
    (net (code "108") (name "unconnected-(U$7-PPT_VBAT-PadP$4)") (class "Default")
      (node (ref "U$7") (pin "P$4") (pinfunction "PPT_VBAT_P$4") (pintype "bidirectional"))
    )
    (net (code "109") (name "unconnected-(U$7-PPT_VBAT-PadP$5)") (class "Default")
      (node (ref "U$7") (pin "P$5") (pinfunction "PPT_VBAT_P$5") (pintype "bidirectional"))
    )
    (net (code "110") (name "unconnected-(U$7-PPT_VBAT-PadP$7)") (class "Default")
      (node (ref "U$7") (pin "P$7") (pinfunction "PPT_VBAT_P$7") (pintype "bidirectional"))
    )
    (net (code "111") (name "unconnected-(U$7-PPT_VBAT-PadP$10)") (class "Default")
      (node (ref "U$7") (pin "P$10") (pinfunction "PPT_VBAT_P$10") (pintype "bidirectional"))
    )
    (net (code "112") (name "unconnected-(U$7-PPT_VBAT-PadP$12)") (class "Default")
      (node (ref "U$7") (pin "P$12") (pinfunction "PPT_VBAT_P$12") (pintype "bidirectional"))
    )
    (net (code "113") (name "unconnected-(U$7-PPT_VBAT-PadP$13)") (class "Default")
      (node (ref "U$7") (pin "P$13") (pinfunction "PPT_VBAT_P$13") (pintype "bidirectional"))
    )
    (net (code "114") (name "unconnected-(U$7-PPT_VBAT-PadP$15)") (class "Default")
      (node (ref "U$7") (pin "P$15") (pinfunction "PPT_VBAT_P$15") (pintype "bidirectional"))
    )
    (net (code "115") (name "unconnected-(U$7-PadP$33)") (class "Default")
      (node (ref "U$7") (pin "P$33") (pinfunction "P$33_P$33") (pintype "bidirectional"))
    )
    (net (code "116") (name "unconnected-(U$7-PadP$34)") (class "Default")
      (node (ref "U$7") (pin "P$34") (pinfunction "P$34_P$34") (pintype "bidirectional"))
    )
    (net (code "117") (name "unconnected-(U$7-PadP$35)") (class "Default")
      (node (ref "U$7") (pin "P$35") (pinfunction "P$35_P$35") (pintype "bidirectional"))
    )
    (net (code "118") (name "unconnected-(U$7-PadP$36)") (class "Default")
      (node (ref "U$7") (pin "P$36") (pinfunction "P$36_P$36") (pintype "bidirectional"))
    )
    (net (code "119") (name "unconnected-(U$7-PadP$37)") (class "Default")
      (node (ref "U$7") (pin "P$37") (pinfunction "P$37_P$37") (pintype "bidirectional"))
    )
    (net (code "120") (name "unconnected-(U$7-PadP$38)") (class "Default")
      (node (ref "U$7") (pin "P$38") (pinfunction "P$38_P$38") (pintype "bidirectional"))
    )
    (net (code "121") (name "unconnected-(U$7-PadP$39)") (class "Default")
      (node (ref "U$7") (pin "P$39") (pinfunction "P$39_P$39") (pintype "bidirectional"))
    )
    (net (code "122") (name "unconnected-(U$7-PadP$40)") (class "Default")
      (node (ref "U$7") (pin "P$40") (pinfunction "P$40_P$40") (pintype "bidirectional"))
    )
    (net (code "123") (name "unconnected-(U$7-PadP$41)") (class "Default")
      (node (ref "U$7") (pin "P$41") (pinfunction "P$41_P$41") (pintype "bidirectional"))
    )
    (net (code "124") (name "unconnected-(U$7-PadP$42)") (class "Default")
      (node (ref "U$7") (pin "P$42") (pinfunction "P$42_P$42") (pintype "bidirectional"))
    )
    (net (code "125") (name "unconnected-(U$7-PadP$43)") (class "Default")
      (node (ref "U$7") (pin "P$43") (pinfunction "P$43_P$43") (pintype "bidirectional"))
    )
    (net (code "126") (name "unconnected-(U$7-PadP$44)") (class "Default")
      (node (ref "U$7") (pin "P$44") (pinfunction "P$44_P$44") (pintype "bidirectional"))
    )
    (net (code "127") (name "unconnected-(U$7-PadP$48)") (class "Default")
      (node (ref "U$7") (pin "P$48") (pinfunction "P$48_P$48") (pintype "bidirectional"))
    )
    (net (code "128") (name "unconnected-(U$7-PadP$52)") (class "Default")
      (node (ref "U$7") (pin "P$52") (pinfunction "P$52_P$52") (pintype "bidirectional"))
    )
    (net (code "129") (name "unconnected-(U$7-PadP$56)") (class "Default")
      (node (ref "U$7") (pin "P$56") (pinfunction "P$56_P$56") (pintype "bidirectional"))
    )
    (net (code "130") (name "unconnected-(U$7-PadP$60)") (class "Default")
      (node (ref "U$7") (pin "P$60") (pinfunction "P$60_P$60") (pintype "bidirectional"))
    )
    (net (code "131") (name "unconnected-(U$7-PadP$61)") (class "Default")
      (node (ref "U$7") (pin "P$61") (pinfunction "P$61_P$61") (pintype "bidirectional"))
    )
    (net (code "132") (name "unconnected-(U$7-PadP$62)") (class "Default")
      (node (ref "U$7") (pin "P$62") (pinfunction "P$62_P$62") (pintype "bidirectional"))
    )
    (net (code "133") (name "unconnected-(U$7-PadP$63)") (class "Default")
      (node (ref "U$7") (pin "P$63") (pinfunction "P$63_P$63") (pintype "bidirectional"))
    )
    (net (code "134") (name "unconnected-(U$7-PadP$64)") (class "Default")
      (node (ref "U$7") (pin "P$64") (pinfunction "P$64_P$64") (pintype "bidirectional"))
    )
    (net (code "135") (name "unconnected-(U$7-PadP$65)") (class "Default")
      (node (ref "U$7") (pin "P$65") (pinfunction "P$65_P$65") (pintype "bidirectional"))
    )
    (net (code "136") (name "unconnected-(U$7-PadP$66)") (class "Default")
      (node (ref "U$7") (pin "P$66") (pinfunction "P$66_P$66") (pintype "bidirectional"))
    )
    (net (code "137") (name "unconnected-(U$7-PadP$67)") (class "Default")
      (node (ref "U$7") (pin "P$67") (pinfunction "P$67_P$67") (pintype "bidirectional"))
    )
    (net (code "138") (name "unconnected-(U$7-PadP$68)") (class "Default")
      (node (ref "U$7") (pin "P$68") (pinfunction "P$68_P$68") (pintype "bidirectional"))
    )
    (net (code "139") (name "unconnected-(U$7-PadP$71)") (class "Default")
      (node (ref "U$7") (pin "P$71") (pinfunction "P$71_P$71") (pintype "bidirectional"))
    )
    (net (code "140") (name "unconnected-(U$7-PadP$72)") (class "Default")
      (node (ref "U$7") (pin "P$72") (pinfunction "P$72_P$72") (pintype "bidirectional"))
    )
    (net (code "141") (name "unconnected-(U$7-PadP$76)") (class "Default")
      (node (ref "U$7") (pin "P$76") (pinfunction "P$76_P$76") (pintype "bidirectional"))
    )
    (net (code "142") (name "unconnected-(U$7-PadP$91)") (class "Default")
      (node (ref "U$7") (pin "P$91") (pinfunction "P$91_P$91") (pintype "bidirectional"))
    )
    (net (code "143") (name "unconnected-(U$7-PadP$92)") (class "Default")
      (node (ref "U$7") (pin "P$92") (pinfunction "P$92_P$92") (pintype "bidirectional"))
    )
    (net (code "144") (name "unconnected-(U$7-PadP$95)") (class "Default")
      (node (ref "U$7") (pin "P$95") (pinfunction "P$95_P$95") (pintype "bidirectional"))
    )
    (net (code "145") (name "unconnected-(U$7-PadP$96)") (class "Default")
      (node (ref "U$7") (pin "P$96") (pinfunction "P$96_P$96") (pintype "bidirectional"))
    )
    (net (code "146") (name "unconnected-(U$7-RAHS_GND-PadP$94)") (class "Default")
      (node (ref "U$7") (pin "P$94") (pinfunction "RAHS_GND_P$94") (pintype "bidirectional"))
    )
    (net (code "147") (name "unconnected-(U$7-RAHS_VBAT-PadP$93)") (class "Default")
      (node (ref "U$7") (pin "P$93") (pinfunction "RAHS_VBAT_P$93") (pintype "bidirectional"))
    )
  )
)
